# SX2PC_free.net
KiCad netlist of a schematic drawn in EAGLE
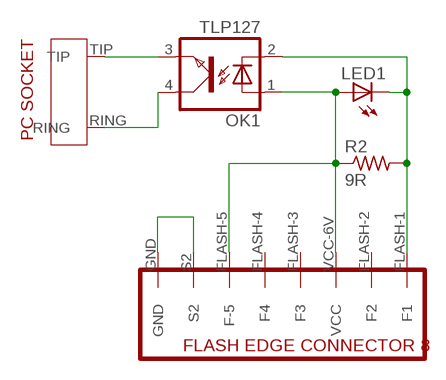
[diagram p0: schematic, sheet 1]

(export (version "E")
  (design (tool "Eeschema 10.0.6"))
  (components
    (comp (ref "LED1")
      (value "LEDCHIP-LED0805")
      (footprint "eagle-import:CHIP-LED0805")
      (libsource (lib "eagle-import") (part "LEDCHIP-LED0805"))
    )
    (comp (ref "OK1")
      (value "TLP127")
      (footprint "eagle-import:SO-4")
      (libsource (lib "eagle-import") (part "TLP127"))
    )
    (comp (ref "R2")
      (value "9R")
      (footprint "eagle-import:R0603")
      (libsource (lib "eagle-import") (part "R-US_R0603"))
    )
    (comp (ref "U$1")
      (value "SX70-FLASH-EDGE8-MALE")
      (footprint "eagle-import:SX70-FLASH-EDGE8")
      (libsource (lib "eagle-import") (part "SX70-FLASH-EDGE8-MALE"))
    )
    (comp (ref "U$2")
      (value "PC-SOCKET-KAISER-1311")
      (footprint "eagle-import:PC-SOCKET-KAISER-1311")
      (libsource (lib "eagle-import") (part "PC-SOCKET-KAISER-1311"))
    )
  )
  (nets
    (net (code "1") (name "Net-(OK1-A)") (class "Default")
      (node (ref "LED1") (pin "A") (pinfunction "A_A") (pintype "passive"))
      (node (ref "OK1") (pin "1") (pinfunction "A_1") (pintype "passive"))
      (node (ref "R2") (pin "1") (pinfunction "1_1") (pintype "passive"))
      (node (ref "U$1") (pin "FLASH-5") (pinfunction "F-5_FLASH-5") (pintype "bidirectional"))
      (node (ref "U$1") (pin "VCC-6V") (pinfunction "VCC_VCC-6V") (pintype "bidirectional"))
    )
    (net (code "2") (name "Net-(OK1-C)") (class "Default")
      (node (ref "LED1") (pin "C") (pinfunction "C_C") (pintype "passive"))
      (node (ref "OK1") (pin "2") (pinfunction "C_2") (pintype "passive"))
      (node (ref "R2") (pin "2") (pinfunction "2_2") (pintype "passive"))
      (node (ref "U$1") (pin "FLASH-1") (pinfunction "F1_FLASH-1") (pintype "bidirectional"))
    )
    (net (code "3") (name "Net-(OK1-COL)") (class "Default")
      (node (ref "OK1") (pin "4") (pinfunction "COL_4") (pintype "passive"))
      (node (ref "U$2") (pin "RING") (pinfunction "RING_RING") (pintype "bidirectional"))
    )
    (net (code "4") (name "Net-(OK1-EMIT)") (class "Default")
      (node (ref "OK1") (pin "3") (pinfunction "EMIT_3") (pintype "passive"))
      (node (ref "U$2") (pin "TIP") (pinfunction "TIP_TIP") (pintype "bidirectional"))
    )
    (net (code "5") (name "Net-(U$1-PadGND)") (class "Default")
      (node (ref "U$1") (pin "GND") (pinfunction "GND_GND") (pintype "bidirectional"))
      (node (ref "U$1") (pin "S2") (pinfunction "S2_S2") (pintype "bidirectional"))
    )
    (net (code "6") (name "unconnected-(U$1-F2-PadFLASH-2)") (class "Default")
      (node (ref "U$1") (pin "FLASH-2") (pinfunction "F2_FLASH-2") (pintype "bidirectional"))
    )
    (net (code "7") (name "unconnected-(U$1-F3-PadFLASH-3)") (class "Default")
      (node (ref "U$1") (pin "FLASH-3") (pinfunction "F3_FLASH-3") (pintype "bidirectional"))
    )
    (net (code "8") (name "unconnected-(U$1-F4-PadFLASH-4)") (class "Default")
      (node (ref "U$1") (pin "FLASH-4") (pinfunction "F4_FLASH-4") (pintype "bidirectional"))
    )
  )
)
